# MCU.net
KiCad netlist of a schematic drawn in Altium Designer
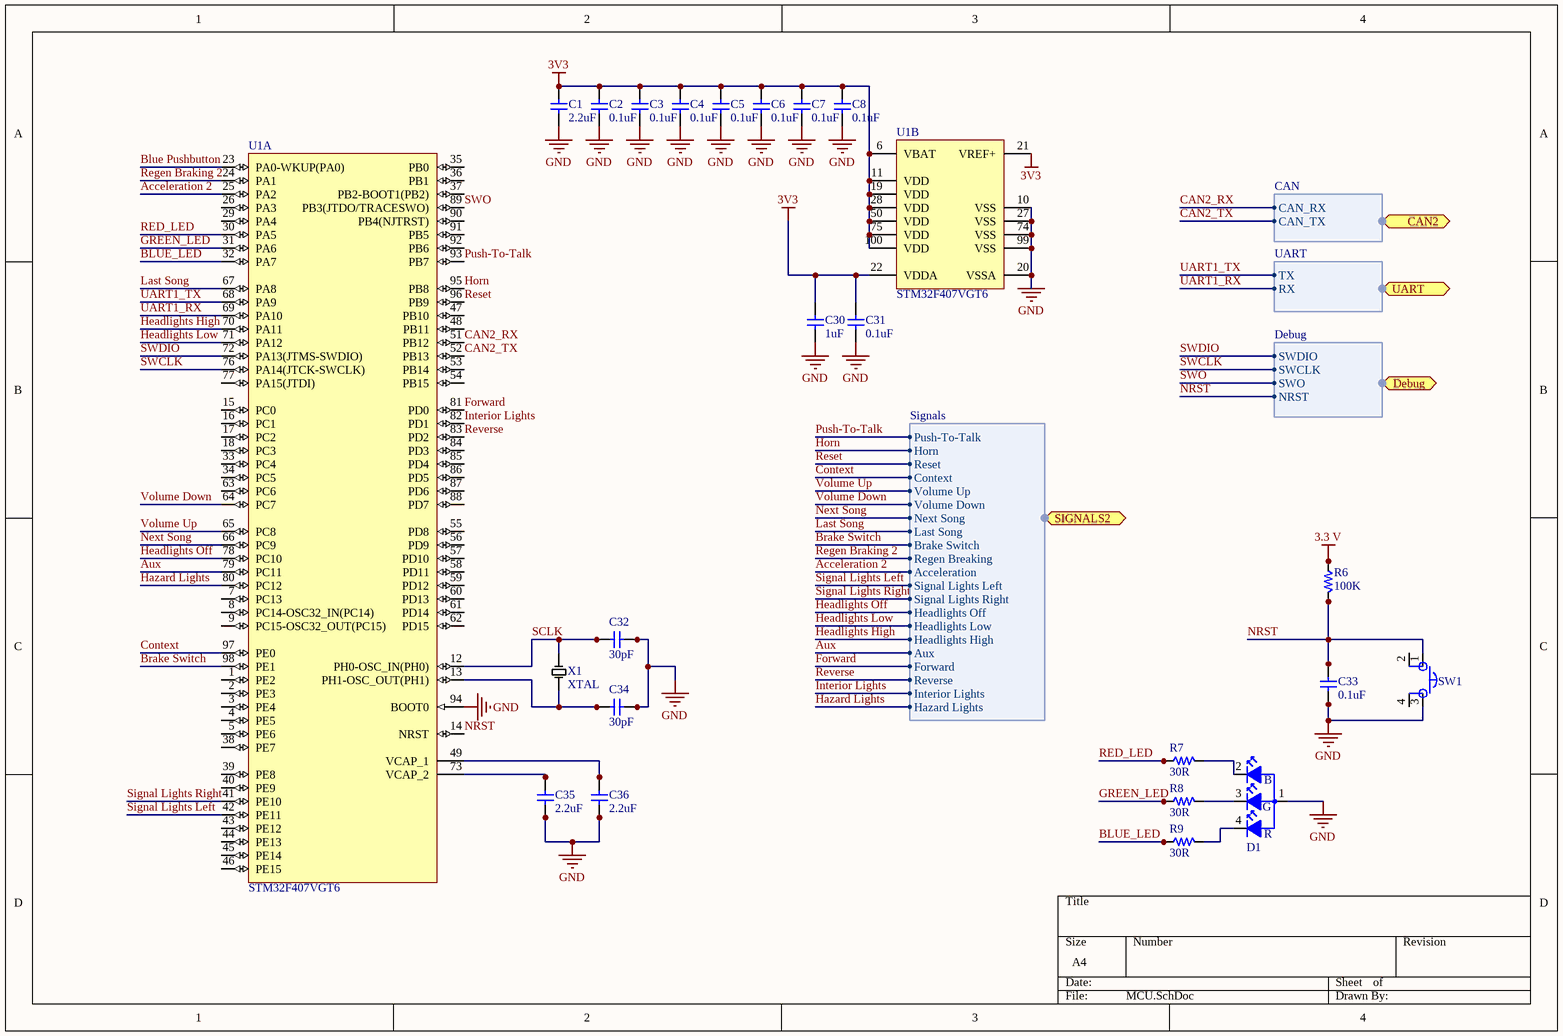
[diagram p0: MCU.SchDoc]

(export (version "E")
  (design (tool "Eeschema 10.0.6"))
  (components
    (comp (ref "C1")
      (value "2.2uF")
      (footprint "PCB_GENERIC_SMD_0603")
      (description "CAP CER 0603 2.2uF 16V X5R 20%")
      (fields (field (name "TOLERANCE") "20%") (field (name "VOLTAGE") "16V"))
      (libsource (lib "CAP-0603") (part "C060-002U2-00"))
    )
    (comp (ref "C2")
      (value "0.1uF")
      (footprint "PCB_GENERIC_SMD_0603")
      (description "CAP CER 0603 0.1uF 16V X5R 20%")
      (fields (field (name "TOLERANCE") "20%") (field (name "VOLTAGE") "16V"))
      (libsource (lib "CAP-0603 (1)") (part "C060-000U1-00"))
    )
    (comp (ref "C3")
      (value "0.1uF")
      (footprint "PCB_GENERIC_SMD_0603")
      (description "CAP CER 0603 0.1uF 16V X5R 20%")
      (fields (field (name "TOLERANCE") "20%") (field (name "VOLTAGE") "16V"))
      (libsource (lib "CAP-0603 (1)") (part "C060-000U1-00"))
    )
    (comp (ref "C4")
      (value "0.1uF")
      (footprint "PCB_GENERIC_SMD_0603")
      (description "CAP CER 0603 0.1uF 16V X5R 20%")
      (fields (field (name "TOLERANCE") "20%") (field (name "VOLTAGE") "16V"))
      (libsource (lib "CAP-0603 (1)") (part "C060-000U1-00"))
    )
    (comp (ref "C5")
      (value "0.1uF")
      (footprint "PCB_GENERIC_SMD_0603")
      (description "CAP CER 0603 0.1uF 16V X5R 20%")
      (fields (field (name "TOLERANCE") "20%") (field (name "VOLTAGE") "16V"))
      (libsource (lib "CAP-0603 (1)") (part "C060-000U1-00"))
    )
    (comp (ref "C6")
      (value "0.1uF")
      (footprint "PCB_GENERIC_SMD_0603")
      (description "CAP CER 0603 0.1uF 16V X5R 20%")
      (fields (field (name "TOLERANCE") "20%") (field (name "VOLTAGE") "16V"))
      (libsource (lib "CAP-0603 (1)") (part "C060-000U1-00"))
    )
    (comp (ref "C7")
      (value "0.1uF")
      (footprint "PCB_GENERIC_SMD_0603")
      (description "CAP CER 0603 0.1uF 16V X5R 20%")
      (fields (field (name "TOLERANCE") "20%") (field (name "VOLTAGE") "16V"))
      (libsource (lib "CAP-0603 (1)") (part "C060-000U1-00"))
    )
    (comp (ref "C8")
      (value "0.1uF")
      (footprint "PCB_GENERIC_SMD_0603")
      (description "CAP CER 0603 0.1uF 16V X5R 20%")
      (fields (field (name "TOLERANCE") "20%") (field (name "VOLTAGE") "16V"))
      (libsource (lib "CAP-0603 (1)") (part "C060-000U1-00"))
    )
    (comp (ref "C30")
      (value "1uF")
      (footprint "PCB_GENERIC_SMD_0603")
      (description "CAP CER 0603 1uF 16V X5R 20%")
      (fields (field (name "TOLERANCE") "20%") (field (name "VOLTAGE") "16V"))
      (libsource (lib "CAP-0603") (part "C060-0001U-00"))
    )
    (comp (ref "C31")
      (value "0.1uF")
      (footprint "PCB_GENERIC_SMD_0603")
      (description "CAP CER 0603 0.1uF 16V X5R 20%")
      (fields (field (name "TOLERANCE") "20%") (field (name "VOLTAGE") "16V"))
      (libsource (lib "CAP-0603 (1)") (part "C060-000U1-00"))
    )
    (comp (ref "C32")
      (value "30pF")
      (footprint "PCB_GENERIC_SMD_0603")
      (description "CAP CER 0603 30pF 50V NP0 5%")
      (fields (field (name "TOLERANCE") "5%") (field (name "VOLTAGE") "50V"))
      (libsource (lib "CAP-0603 (2)") (part "C060-0030P-00"))
    )
    (comp (ref "C33")
      (value "0.1uF")
      (footprint "PCB_GENERIC_SMD_0603")
      (description "CAP CER 0603 0.1uF 16V X5R 20%")
      (fields (field (name "TOLERANCE") "20%") (field (name "VOLTAGE") "16V"))
      (libsource (lib "CAP-0603 (2)") (part "C060-000U1-00"))
    )
    (comp (ref "C34")
      (value "30pF")
      (footprint "PCB_GENERIC_SMD_0603")
      (description "CAP CER 0603 30pF 50V NP0 5%")
      (fields (field (name "TOLERANCE") "5%") (field (name "VOLTAGE") "50V"))
      (libsource (lib "CAP-0603 (2)") (part "C060-0030P-00"))
    )
    (comp (ref "C35")
      (value "2.2uF")
      (footprint "PCB_GENERIC_SMD_0603")
      (description "CAP CER 0603 2.2uF 16V X5R 20%")
      (fields (field (name "TOLERANCE") "20%") (field (name "VOLTAGE") "16V"))
      (libsource (lib "CAP-0603 (2)") (part "C060-002U2-00"))
    )
    (comp (ref "C36")
      (value "2.2uF")
      (footprint "PCB_GENERIC_SMD_0603")
      (description "CAP CER 0603 2.2uF 16V X5R 20%")
      (fields (field (name "TOLERANCE") "20%") (field (name "VOLTAGE") "16V"))
      (libsource (lib "CAP-0603 (2)") (part "C060-002U2-00"))
    )
    (comp (ref "D1")
      (value "D0S4-000CR-00")
      (footprint "CLMVB-FKA")
      (description "LED 4SMD RGB 2Vf 3Vf 3Vf 20mA 10mA 10mA")
      (libsource (lib "LED-4SMD") (part "D0S4-000CR-00"))
    )
    (comp (ref "R6")
      (value "100K")
      (footprint "PCB_GENERIC_SMD_0603")
      (description "RES 0603 100K 5% 63mW")
      (fields (field (name "TOLERANCE") "5%") (field (name "POWER") "63mW"))
      (libsource (lib "RES-0603") (part "R060-00104-05"))
    )
    (comp (ref "R7")
      (value "30R")
      (footprint "PCB_GENERIC_SMD_0603")
      (description "RES 0603 30ohm 5% 100mW")
      (fields (field (name "TOLERANCE") "5%") (field (name "POWER") "100mW"))
      (libsource (lib "RES-0603") (part "R060-00300-05"))
    )
    (comp (ref "R8")
      (value "30R")
      (footprint "PCB_GENERIC_SMD_0603")
      (description "RES 0603 30ohm 5% 100mW")
      (fields (field (name "TOLERANCE") "5%") (field (name "POWER") "100mW"))
      (libsource (lib "RES-0603") (part "R060-00300-05"))
    )
    (comp (ref "R9")
      (value "30R")
      (footprint "PCB_GENERIC_SMD_0603")
      (description "RES 0603 30ohm 5% 100mW")
      (fields (field (name "TOLERANCE") "5%") (field (name "POWER") "100mW"))
      (libsource (lib "RES-0603") (part "R060-00300-05"))
    )
    (comp (ref "SW1")
      (value "Tactile Switch")
      (footprint "C&K 4 pin Tactile Switch")
      (libsource (lib "C&K 4 Pin Tactile Switch") (part "C&K Tactile Switch"))
    )
    (comp (ref "U1")
      (value "STM32F407VGT6")
      (footprint "STM-LQFP100_M")
      (fields (field (name "MANUFACTURER") "STMicroelectronics"))
      (libsource (lib "STMicroelectronics STM32 F4") (part "STM32F407VGT6"))
    )
    (comp (ref "X1") (value "XTAL") (footprint "CRYSTAL_8MHZ") (libsource (lib "Crystal") (part "Crystal")))
  )
  (nets
    (net (code "5") (name "/Acceleration 2") (class "Default")
      (node (ref "U1") (pin "25") (pinfunction "PA2_25") (pintype "bidirectional"))
    )
    (net (code "6") (name "/Aux") (class "Default")
      (node (ref "U1") (pin "79") (pinfunction "PC11_79") (pintype "bidirectional"))
    )
    (net (code "7") (name "/BLUE_LED") (class "Default")
      (node (ref "R9") (pin "1") (pinfunction "1_1") (pintype "passive"))
      (node (ref "U1") (pin "32") (pinfunction "PA7_32") (pintype "bidirectional"))
    )
    (net (code "8") (name "/Blue Pushbutton") (class "Default")
      (node (ref "U1") (pin "23") (pinfunction "PA0-WKUP(PA0)_23") (pintype "bidirectional"))
    )
    (net (code "9") (name "/Brake Switch") (class "Default")
      (node (ref "U1") (pin "98") (pinfunction "PE1_98") (pintype "bidirectional"))
    )
    (net (code "10") (name "/CAN2_RX") (class "Default")
      (node (ref "U1") (pin "51") (pinfunction "PB12_51") (pintype "bidirectional"))
    )
    (net (code "11") (name "/CAN2_TX") (class "Default")
      (node (ref "U1") (pin "52") (pinfunction "PB13_52") (pintype "bidirectional"))
    )
    (net (code "12") (name "/Context") (class "Default")
      (node (ref "U1") (pin "97") (pinfunction "PE0_97") (pintype "bidirectional"))
    )
    (net (code "13") (name "/Forward") (class "Default")
      (node (ref "U1") (pin "81") (pinfunction "PD0_81") (pintype "bidirectional"))
    )
    (net (code "14") (name "/GREEN_LED") (class "Default")
      (node (ref "R8") (pin "1") (pinfunction "1_1") (pintype "passive"))
      (node (ref "U1") (pin "31") (pinfunction "PA6_31") (pintype "bidirectional"))
    )
    (net (code "15") (name "/Hazard Lights") (class "Default")
      (node (ref "U1") (pin "80") (pinfunction "PC12_80") (pintype "bidirectional"))
    )
    (net (code "16") (name "/Headlights High") (class "Default")
      (node (ref "U1") (pin "70") (pinfunction "PA11_70") (pintype "bidirectional"))
    )
    (net (code "17") (name "/Headlights Low") (class "Default")
      (node (ref "U1") (pin "71") (pinfunction "PA12_71") (pintype "bidirectional"))
    )
    (net (code "18") (name "/Headlights Off") (class "Default")
      (node (ref "U1") (pin "78") (pinfunction "PC10_78") (pintype "bidirectional"))
    )
    (net (code "19") (name "/Horn") (class "Default")
      (node (ref "U1") (pin "95") (pinfunction "PB8_95") (pintype "bidirectional"))
    )
    (net (code "20") (name "/Interior Lights") (class "Default")
      (node (ref "U1") (pin "82") (pinfunction "PD1_82") (pintype "bidirectional"))
    )
    (net (code "21") (name "/Last Song") (class "Default")
      (node (ref "U1") (pin "67") (pinfunction "PA8_67") (pintype "bidirectional"))
    )
    (net (code "22") (name "/NRST") (class "Default")
      (node (ref "C33") (pin "1") (pinfunction "1_1") (pintype "passive"))
      (node (ref "R6") (pin "2") (pinfunction "2_2") (pintype "passive"))
      (node (ref "SW1") (pin "1") (pinfunction "1_1") (pintype "passive"))
      (node (ref "U1") (pin "14") (pinfunction "NRST_14") (pintype "bidirectional"))
    )
    (net (code "23") (name "/Next Song") (class "Default")
      (node (ref "U1") (pin "66") (pinfunction "PC9_66") (pintype "bidirectional"))
    )
    (net (code "24") (name "/Push-To-Talk") (class "Default")
      (node (ref "U1") (pin "93") (pinfunction "PB7_93") (pintype "bidirectional"))
    )
    (net (code "25") (name "/RED_LED") (class "Default")
      (node (ref "R7") (pin "1") (pinfunction "1_1") (pintype "passive"))
      (node (ref "U1") (pin "30") (pinfunction "PA5_30") (pintype "bidirectional"))
    )
    (net (code "26") (name "/Regen Braking 2") (class "Default")
      (node (ref "U1") (pin "24") (pinfunction "PA1_24") (pintype "bidirectional"))
    )
    (net (code "27") (name "/Reset") (class "Default")
      (node (ref "U1") (pin "96") (pinfunction "PB9_96") (pintype "bidirectional"))
    )
    (net (code "28") (name "/Reverse") (class "Default")
      (node (ref "U1") (pin "83") (pinfunction "PD2_83") (pintype "bidirectional"))
    )
    (net (code "29") (name "/SCLK") (class "Default")
      (node (ref "C32") (pin "2") (pinfunction "2_2") (pintype "passive"))
      (node (ref "U1") (pin "12") (pinfunction "PH0-OSC_IN(PH0)_12") (pintype "bidirectional"))
      (node (ref "X1") (pin "1") (pintype "passive"))
    )
    (net (code "30") (name "/SWCLK") (class "Default")
      (node (ref "U1") (pin "76") (pinfunction "PA14(JTCK-SWCLK)_76") (pintype "bidirectional"))
    )
    (net (code "31") (name "/SWDIO") (class "Default")
      (node (ref "U1") (pin "72") (pinfunction "PA13(JTMS-SWDIO)_72") (pintype "bidirectional"))
    )
    (net (code "32") (name "/SWO") (class "Default")
      (node (ref "U1") (pin "89") (pinfunction "PB3(JTDO/TRACESWO)_89") (pintype "bidirectional"))
    )
    (net (code "33") (name "/Signal Lights Left") (class "Default")
      (node (ref "U1") (pin "42") (pinfunction "PE11_42") (pintype "bidirectional"))
    )
    (net (code "34") (name "/Signal Lights Right") (class "Default")
      (node (ref "U1") (pin "41") (pinfunction "PE10_41") (pintype "bidirectional"))
    )
    (net (code "35") (name "/UART1_RX") (class "Default")
      (node (ref "U1") (pin "69") (pinfunction "PA10_69") (pintype "bidirectional"))
    )
    (net (code "36") (name "/UART1_TX") (class "Default")
      (node (ref "U1") (pin "68") (pinfunction "PA9_68") (pintype "bidirectional"))
    )
    (net (code "37") (name "/Volume Down") (class "Default")
      (node (ref "U1") (pin "64") (pinfunction "PC7_64") (pintype "bidirectional"))
    )
    (net (code "38") (name "/Volume Up") (class "Default")
      (node (ref "U1") (pin "65") (pinfunction "PC8_65") (pintype "bidirectional"))
    )
    (net (code "43") (name "3.3 V") (class "Default")
      (node (ref "R6") (pin "1") (pinfunction "1_1") (pintype "passive"))
    )
    (net (code "44") (name "3V3") (class "Default")
      (node (ref "C1") (pin "2") (pinfunction "2_2") (pintype "passive"))
      (node (ref "C2") (pin "2") (pinfunction "2_2") (pintype "passive"))
      (node (ref "C3") (pin "2") (pinfunction "2_2") (pintype "passive"))
      (node (ref "C30") (pin "2") (pinfunction "2_2") (pintype "passive"))
      (node (ref "C31") (pin "2") (pinfunction "2_2") (pintype "passive"))
      (node (ref "C4") (pin "2") (pinfunction "2_2") (pintype "passive"))
      (node (ref "C5") (pin "2") (pinfunction "2_2") (pintype "passive"))
      (node (ref "C6") (pin "2") (pinfunction "2_2") (pintype "passive"))
      (node (ref "C7") (pin "2") (pinfunction "2_2") (pintype "passive"))
      (node (ref "C8") (pin "2") (pinfunction "2_2") (pintype "passive"))
      (node (ref "U1") (pin "100") (pinfunction "VDD_100") (pintype "power_in"))
      (node (ref "U1") (pin "11") (pinfunction "VDD_11") (pintype "power_in"))
      (node (ref "U1") (pin "19") (pinfunction "VDD_19") (pintype "power_in"))
      (node (ref "U1") (pin "21") (pinfunction "VREF+_21") (pintype "power_in"))
      (node (ref "U1") (pin "22") (pinfunction "VDDA_22") (pintype "power_in"))
      (node (ref "U1") (pin "28") (pinfunction "VDD_28") (pintype "power_in"))
      (node (ref "U1") (pin "50") (pinfunction "VDD_50") (pintype "power_in"))
      (node (ref "U1") (pin "6") (pinfunction "VBAT_6") (pintype "power_in"))
      (node (ref "U1") (pin "75") (pinfunction "VDD_75") (pintype "power_in"))
    )
    (net (code "45") (name "GND") (class "Default")
      (node (ref "C1") (pin "1") (pinfunction "1_1") (pintype "passive"))
      (node (ref "C2") (pin "1") (pinfunction "1_1") (pintype "passive"))
      (node (ref "C3") (pin "1") (pinfunction "1_1") (pintype "passive"))
      (node (ref "C30") (pin "1") (pinfunction "1_1") (pintype "passive"))
      (node (ref "C31") (pin "1") (pinfunction "1_1") (pintype "passive"))
      (node (ref "C32") (pin "1") (pinfunction "1_1") (pintype "passive"))
      (node (ref "C33") (pin "2") (pinfunction "2_2") (pintype "passive"))
      (node (ref "C34") (pin "1") (pinfunction "1_1") (pintype "passive"))
      (node (ref "C35") (pin "1") (pinfunction "1_1") (pintype "passive"))
      (node (ref "C36") (pin "1") (pinfunction "1_1") (pintype "passive"))
      (node (ref "C4") (pin "1") (pinfunction "1_1") (pintype "passive"))
      (node (ref "C5") (pin "1") (pinfunction "1_1") (pintype "passive"))
      (node (ref "C6") (pin "1") (pinfunction "1_1") (pintype "passive"))
      (node (ref "C7") (pin "1") (pinfunction "1_1") (pintype "passive"))
      (node (ref "C8") (pin "1") (pinfunction "1_1") (pintype "passive"))
      (node (ref "D1") (pin "1") (pinfunction "Red_1") (pintype "passive"))
      (node (ref "SW1") (pin "3") (pinfunction "3_3") (pintype "passive"))
      (node (ref "U1") (pin "10") (pinfunction "VSS_10") (pintype "power_in"))
      (node (ref "U1") (pin "20") (pinfunction "VSSA_20") (pintype "power_in"))
      (node (ref "U1") (pin "27") (pinfunction "VSS_27") (pintype "power_in"))
      (node (ref "U1") (pin "74") (pinfunction "VSS_74") (pintype "power_in"))
      (node (ref "U1") (pin "94") (pinfunction "BOOT0_94") (pintype "input"))
      (node (ref "U1") (pin "99") (pinfunction "VSS_99") (pintype "power_in"))
    )
    (net (code "46") (name "Net-(D1-Blue)") (class "Default")
      (node (ref "D1") (pin "3") (pinfunction "Blue_3") (pintype "passive"))
      (node (ref "R8") (pin "2") (pinfunction "2_2") (pintype "passive"))
    )
    (net (code "47") (name "Net-(D1-Green)") (class "Default")
      (node (ref "D1") (pin "2") (pinfunction "Green_2") (pintype "passive"))
      (node (ref "R7") (pin "2") (pinfunction "2_2") (pintype "passive"))
    )
    (net (code "48") (name "Net-(D1-Pad4)") (class "Default")
      (node (ref "D1") (pin "4") (pinfunction "4_4") (pintype "passive"))
      (node (ref "R9") (pin "2") (pinfunction "2_2") (pintype "passive"))
    )
    (net (code "49") (name "Net-(U1A-PH1-OSC_OUT(PH1))") (class "Default")
      (node (ref "C34") (pin "2") (pinfunction "2_2") (pintype "passive"))
      (node (ref "U1") (pin "13") (pinfunction "PH1-OSC_OUT(PH1)_13") (pintype "bidirectional"))
      (node (ref "X1") (pin "2") (pintype "passive"))
    )
    (net (code "50") (name "Net-(U1A-VCAP_1)") (class "Default")
      (node (ref "C36") (pin "2") (pinfunction "2_2") (pintype "passive"))
      (node (ref "U1") (pin "49") (pinfunction "VCAP_1_49") (pintype "power_in"))
    )
    (net (code "51") (name "Net-(U1A-VCAP_2)") (class "Default")
      (node (ref "C35") (pin "2") (pinfunction "2_2") (pintype "passive"))
      (node (ref "U1") (pin "73") (pinfunction "VCAP_2_73") (pintype "power_in"))
    )
    (net (code "52") (name "unconnected-(SW1-Pad2)") (class "Default")
      (node (ref "SW1") (pin "2") (pinfunction "2_2") (pintype "passive"))
    )
    (net (code "53") (name "unconnected-(SW1-Pad4)") (class "Default")
      (node (ref "SW1") (pin "4") (pinfunction "4_4") (pintype "passive"))
    )
    (net (code "54") (name "unconnected-(U1A-PA3-Pad26)") (class "Default")
      (node (ref "U1") (pin "26") (pinfunction "PA3_26") (pintype "bidirectional"))
    )
    (net (code "55") (name "unconnected-(U1A-PA4-Pad29)") (class "Default")
      (node (ref "U1") (pin "29") (pinfunction "PA4_29") (pintype "bidirectional"))
    )
    (net (code "56") (name "unconnected-(U1A-PA15(JTDI)-Pad77)") (class "Default")
      (node (ref "U1") (pin "77") (pinfunction "PA15(JTDI)_77") (pintype "bidirectional"))
    )
    (net (code "57") (name "unconnected-(U1A-PB0-Pad35)") (class "Default")
      (node (ref "U1") (pin "35") (pinfunction "PB0_35") (pintype "bidirectional"))
    )
    (net (code "58") (name "unconnected-(U1A-PB1-Pad36)") (class "Default")
      (node (ref "U1") (pin "36") (pinfunction "PB1_36") (pintype "bidirectional"))
    )
    (net (code "59") (name "unconnected-(U1A-PB2-BOOT1(PB2)-Pad37)") (class "Default")
      (node (ref "U1") (pin "37") (pinfunction "PB2-BOOT1(PB2)_37") (pintype "bidirectional"))
    )
    (net (code "60") (name "unconnected-(U1A-PB4(NJTRST)-Pad90)") (class "Default")
      (node (ref "U1") (pin "90") (pinfunction "PB4(NJTRST)_90") (pintype "bidirectional"))
    )
    (net (code "61") (name "unconnected-(U1A-PB5-Pad91)") (class "Default")
      (node (ref "U1") (pin "91") (pinfunction "PB5_91") (pintype "bidirectional"))
    )
    (net (code "62") (name "unconnected-(U1A-PB6-Pad92)") (class "Default")
      (node (ref "U1") (pin "92") (pinfunction "PB6_92") (pintype "bidirectional"))
    )
    (net (code "63") (name "unconnected-(U1A-PB10-Pad47)") (class "Default")
      (node (ref "U1") (pin "47") (pinfunction "PB10_47") (pintype "bidirectional"))
    )
    (net (code "64") (name "unconnected-(U1A-PB11-Pad48)") (class "Default")
      (node (ref "U1") (pin "48") (pinfunction "PB11_48") (pintype "bidirectional"))
    )
    (net (code "65") (name "unconnected-(U1A-PB14-Pad53)") (class "Default")
      (node (ref "U1") (pin "53") (pinfunction "PB14_53") (pintype "bidirectional"))
    )
    (net (code "66") (name "unconnected-(U1A-PB15-Pad54)") (class "Default")
      (node (ref "U1") (pin "54") (pinfunction "PB15_54") (pintype "bidirectional"))
    )
    (net (code "67") (name "unconnected-(U1A-PC0-Pad15)") (class "Default")
      (node (ref "U1") (pin "15") (pinfunction "PC0_15") (pintype "bidirectional"))
    )
    (net (code "68") (name "unconnected-(U1A-PC1-Pad16)") (class "Default")
      (node (ref "U1") (pin "16") (pinfunction "PC1_16") (pintype "bidirectional"))
    )
    (net (code "69") (name "unconnected-(U1A-PC2-Pad17)") (class "Default")
      (node (ref "U1") (pin "17") (pinfunction "PC2_17") (pintype "bidirectional"))
    )
    (net (code "70") (name "unconnected-(U1A-PC3-Pad18)") (class "Default")
      (node (ref "U1") (pin "18") (pinfunction "PC3_18") (pintype "bidirectional"))
    )
    (net (code "71") (name "unconnected-(U1A-PC4-Pad33)") (class "Default")
      (node (ref "U1") (pin "33") (pinfunction "PC4_33") (pintype "bidirectional"))
    )
    (net (code "72") (name "unconnected-(U1A-PC5-Pad34)") (class "Default")
      (node (ref "U1") (pin "34") (pinfunction "PC5_34") (pintype "bidirectional"))
    )
    (net (code "73") (name "unconnected-(U1A-PC6-Pad63)") (class "Default")
      (node (ref "U1") (pin "63") (pinfunction "PC6_63") (pintype "bidirectional"))
    )
    (net (code "74") (name "unconnected-(U1A-PC13-Pad7)") (class "Default")
      (node (ref "U1") (pin "7") (pinfunction "PC13_7") (pintype "bidirectional"))
    )
    (net (code "75") (name "unconnected-(U1A-PC14-OSC32_IN(PC14)-Pad8)") (class "Default")
      (node (ref "U1") (pin "8") (pinfunction "PC14-OSC32_IN(PC14)_8") (pintype "bidirectional"))
    )
    (net (code "76") (name "unconnected-(U1A-PC15-OSC32_OUT(PC15)-Pad9)") (class "Default")
      (node (ref "U1") (pin "9") (pinfunction "PC15-OSC32_OUT(PC15)_9") (pintype "bidirectional"))
    )
    (net (code "77") (name "unconnected-(U1A-PD3-Pad84)") (class "Default")
      (node (ref "U1") (pin "84") (pinfunction "PD3_84") (pintype "bidirectional"))
    )
    (net (code "78") (name "unconnected-(U1A-PD4-Pad85)") (class "Default")
      (node (ref "U1") (pin "85") (pinfunction "PD4_85") (pintype "bidirectional"))
    )
    (net (code "79") (name "unconnected-(U1A-PD5-Pad86)") (class "Default")
      (node (ref "U1") (pin "86") (pinfunction "PD5_86") (pintype "bidirectional"))
    )
    (net (code "80") (name "unconnected-(U1A-PD6-Pad87)") (class "Default")
      (node (ref "U1") (pin "87") (pinfunction "PD6_87") (pintype "bidirectional"))
    )
    (net (code "81") (name "unconnected-(U1A-PD7-Pad88)") (class "Default")
      (node (ref "U1") (pin "88") (pinfunction "PD7_88") (pintype "bidirectional"))
    )
    (net (code "82") (name "unconnected-(U1A-PD8-Pad55)") (class "Default")
      (node (ref "U1") (pin "55") (pinfunction "PD8_55") (pintype "bidirectional"))
    )
    (net (code "83") (name "unconnected-(U1A-PD9-Pad56)") (class "Default")
      (node (ref "U1") (pin "56") (pinfunction "PD9_56") (pintype "bidirectional"))
    )
    (net (code "84") (name "unconnected-(U1A-PD10-Pad57)") (class "Default")
      (node (ref "U1") (pin "57") (pinfunction "PD10_57") (pintype "bidirectional"))
    )
    (net (code "85") (name "unconnected-(U1A-PD11-Pad58)") (class "Default")
      (node (ref "U1") (pin "58") (pinfunction "PD11_58") (pintype "bidirectional"))
    )
    (net (code "86") (name "unconnected-(U1A-PD12-Pad59)") (class "Default")
      (node (ref "U1") (pin "59") (pinfunction "PD12_59") (pintype "bidirectional"))
    )
    (net (code "87") (name "unconnected-(U1A-PD13-Pad60)") (class "Default")
      (node (ref "U1") (pin "60") (pinfunction "PD13_60") (pintype "bidirectional"))
    )
    (net (code "88") (name "unconnected-(U1A-PD14-Pad61)") (class "Default")
      (node (ref "U1") (pin "61") (pinfunction "PD14_61") (pintype "bidirectional"))
    )
    (net (code "89") (name "unconnected-(U1A-PD15-Pad62)") (class "Default")
      (node (ref "U1") (pin "62") (pinfunction "PD15_62") (pintype "bidirectional"))
    )
    (net (code "90") (name "unconnected-(U1A-PE2-Pad1)") (class "Default")
      (node (ref "U1") (pin "1") (pinfunction "PE2_1") (pintype "bidirectional"))
    )
    (net (code "91") (name "unconnected-(U1A-PE3-Pad2)") (class "Default")
      (node (ref "U1") (pin "2") (pinfunction "PE3_2") (pintype "bidirectional"))
    )
    (net (code "92") (name "unconnected-(U1A-PE4-Pad3)") (class "Default")
      (node (ref "U1") (pin "3") (pinfunction "PE4_3") (pintype "bidirectional"))
    )
    (net (code "93") (name "unconnected-(U1A-PE5-Pad4)") (class "Default")
      (node (ref "U1") (pin "4") (pinfunction "PE5_4") (pintype "bidirectional"))
    )
    (net (code "94") (name "unconnected-(U1A-PE6-Pad5)") (class "Default")
      (node (ref "U1") (pin "5") (pinfunction "PE6_5") (pintype "bidirectional"))
    )
    (net (code "95") (name "unconnected-(U1A-PE7-Pad38)") (class "Default")
      (node (ref "U1") (pin "38") (pinfunction "PE7_38") (pintype "bidirectional"))
    )
    (net (code "96") (name "unconnected-(U1A-PE8-Pad39)") (class "Default")
      (node (ref "U1") (pin "39") (pinfunction "PE8_39") (pintype "bidirectional"))
    )
    (net (code "97") (name "unconnected-(U1A-PE9-Pad40)") (class "Default")
      (node (ref "U1") (pin "40") (pinfunction "PE9_40") (pintype "bidirectional"))
    )
    (net (code "98") (name "unconnected-(U1A-PE12-Pad43)") (class "Default")
      (node (ref "U1") (pin "43") (pinfunction "PE12_43") (pintype "bidirectional"))
    )
    (net (code "99") (name "unconnected-(U1A-PE13-Pad44)") (class "Default")
      (node (ref "U1") (pin "44") (pinfunction "PE13_44") (pintype "bidirectional"))
    )
    (net (code "100") (name "unconnected-(U1A-PE14-Pad45)") (class "Default")
      (node (ref "U1") (pin "45") (pinfunction "PE14_45") (pintype "bidirectional"))
    )
    (net (code "101") (name "unconnected-(U1A-PE15-Pad46)") (class "Default")
      (node (ref "U1") (pin "46") (pinfunction "PE15_46") (pintype "bidirectional"))
    )
  )
)
